# M617B.net
KiCad netlist of a schematic drawn in EAGLE
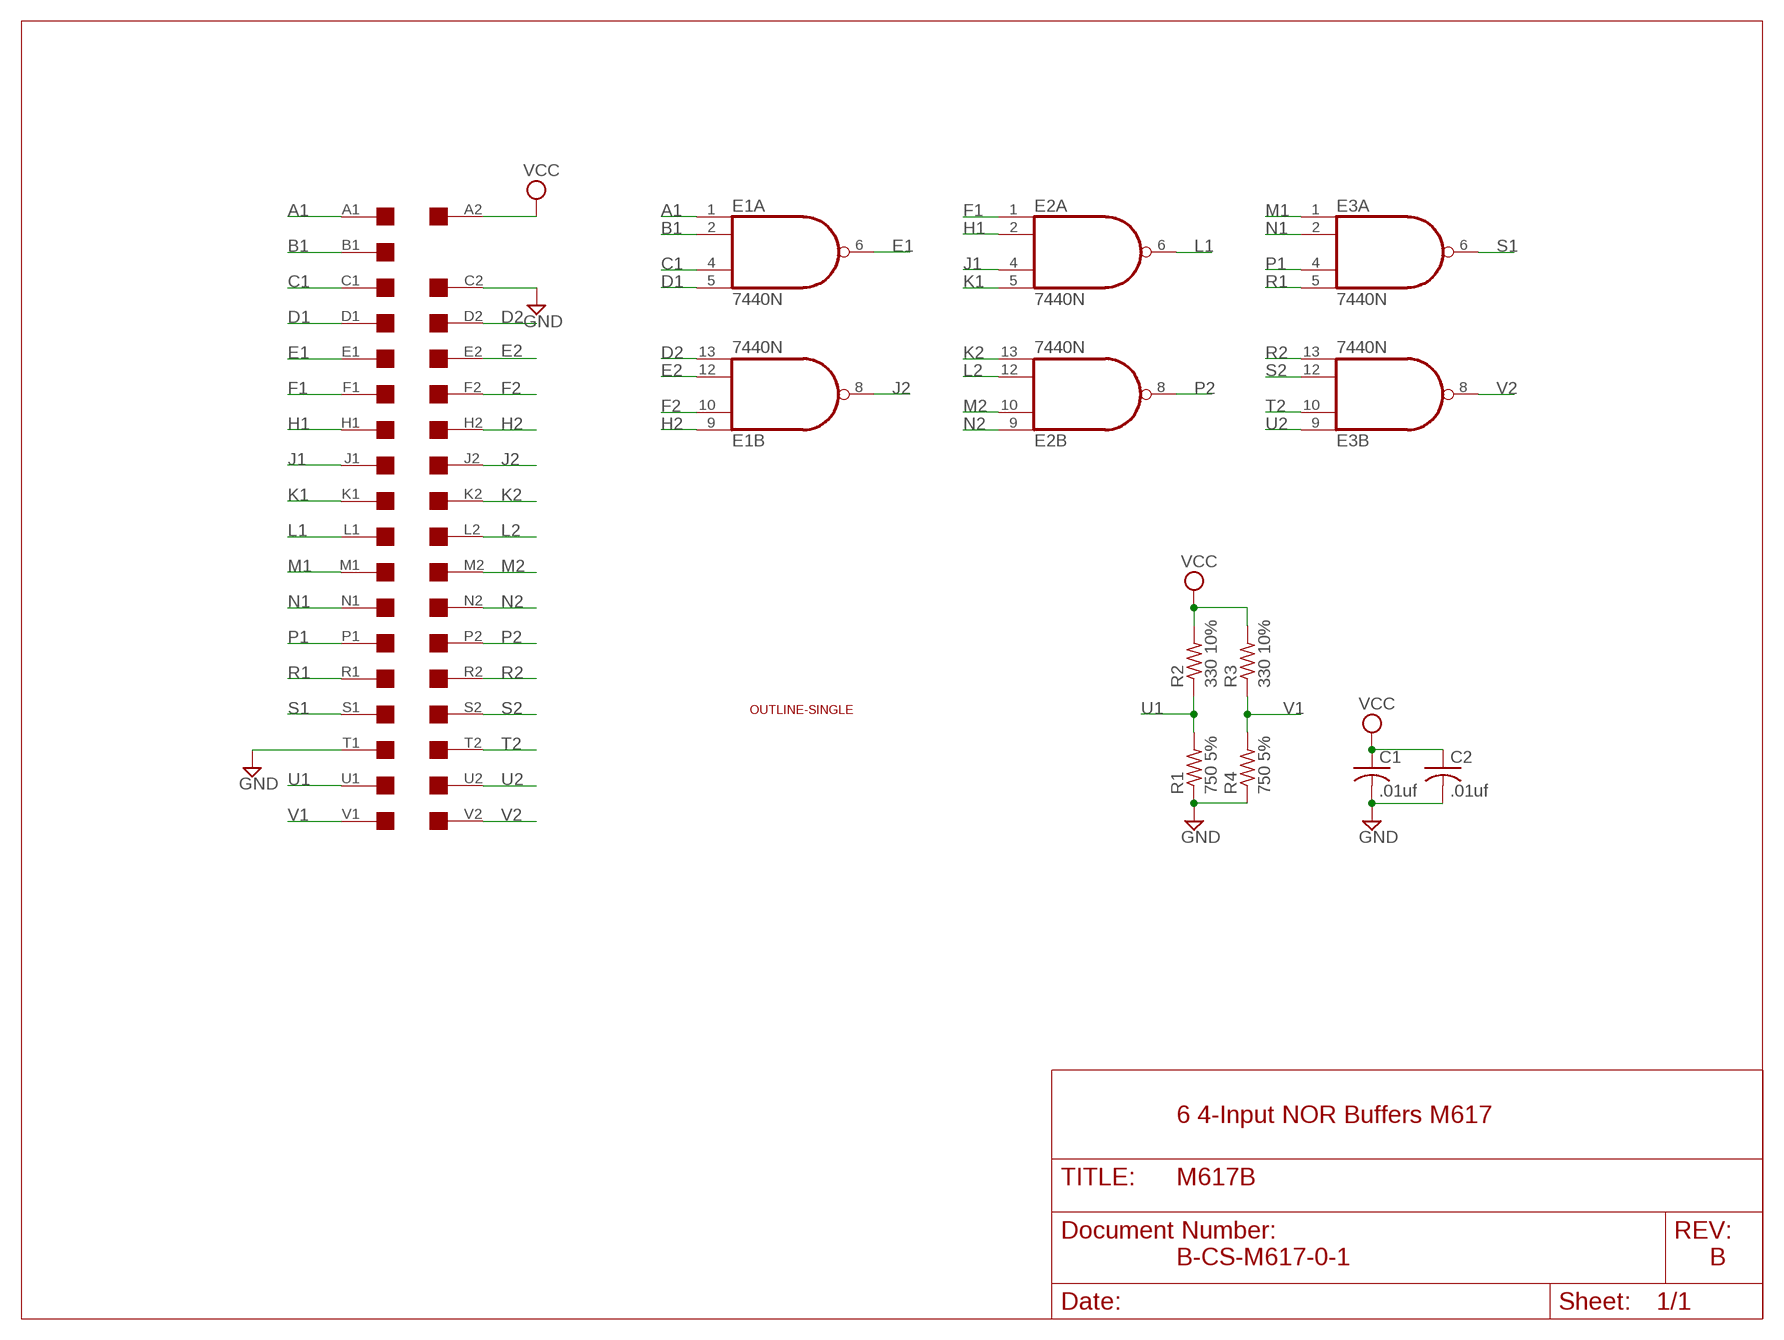
[diagram p0: schematic, sheet 1]

(export (version "E")
  (design (tool "Eeschema 10.0.6"))
  (components
    (comp (ref "C1")
      (value ".01uf")
      (footprint "eagle-import:C075-032X103")
      (libsource (lib "eagle-import") (part "C-US075-032X103"))
    )
    (comp (ref "C2")
      (value ".01uf")
      (footprint "eagle-import:C075-032X103")
      (libsource (lib "eagle-import") (part "C-US075-032X103"))
    )
    (comp (ref "E1")
      (value "7440N")
      (footprint "eagle-import:DIL14")
      (libsource (lib "eagle-import") (part "7420NS"))
    )
    (comp (ref "E2")
      (value "7440N")
      (footprint "eagle-import:DIL14")
      (libsource (lib "eagle-import") (part "7420NS"))
    )
    (comp (ref "E3")
      (value "7440N")
      (footprint "eagle-import:DIL14")
      (libsource (lib "eagle-import") (part "7420NS"))
    )
    (comp (ref "R1")
      (value "750 5%")
      (footprint "eagle-import:0207_15")
      (libsource (lib "eagle-import") (part "R-US_0207/15"))
    )
    (comp (ref "R2")
      (value "330 10%")
      (footprint "eagle-import:0207_15")
      (libsource (lib "eagle-import") (part "R-US_0207/15"))
    )
    (comp (ref "R3")
      (value "330 10%")
      (footprint "eagle-import:0207_15")
      (libsource (lib "eagle-import") (part "R-US_0207/15"))
    )
    (comp (ref "R4")
      (value "750 5%")
      (footprint "eagle-import:0207_15")
      (libsource (lib "eagle-import") (part "R-US_0207/15"))
    )
    (comp (ref "U$1")
      (value "SINGLE")
      (footprint "eagle-import:EDGE-CON2")
      (libsource (lib "eagle-import") (part "SINGLE"))
    )
    (comp (ref "U$4")
      (value "OUTLINE-SINGLE")
      (footprint "eagle-import:SINGLE")
      (libsource (lib "eagle-import") (part "OUTLINE-SINGLE"))
    )
  )
  (nets
    (net (code "1") (name "/A1") (class "Default")
      (node (ref "E1") (pin "1") (pinfunction "I0_1") (pintype "input"))
      (node (ref "U$1") (pin "A1") (pinfunction "1_A1") (pintype "bidirectional"))
    )
    (net (code "2") (name "/B1") (class "Default")
      (node (ref "E1") (pin "2") (pinfunction "I1_2") (pintype "input"))
      (node (ref "U$1") (pin "B1") (pinfunction "1_B1") (pintype "bidirectional"))
    )
    (net (code "3") (name "/C1") (class "Default")
      (node (ref "E1") (pin "4") (pinfunction "I2_4") (pintype "input"))
      (node (ref "U$1") (pin "C1") (pinfunction "1_C1") (pintype "bidirectional"))
    )
    (net (code "4") (name "/D1") (class "Default")
      (node (ref "E1") (pin "5") (pinfunction "I3_5") (pintype "input"))
      (node (ref "U$1") (pin "D1") (pinfunction "1_D1") (pintype "bidirectional"))
    )
    (net (code "5") (name "/D2") (class "Default")
      (node (ref "E1") (pin "13") (pinfunction "I3_13") (pintype "input"))
      (node (ref "U$1") (pin "D2") (pinfunction "1_D2") (pintype "bidirectional"))
    )
    (net (code "6") (name "/E1") (class "Default")
      (node (ref "E1") (pin "6") (pinfunction "O_6") (pintype "output"))
      (node (ref "U$1") (pin "E1") (pinfunction "1_E1") (pintype "bidirectional"))
    )
    (net (code "7") (name "/E2") (class "Default")
      (node (ref "E1") (pin "12") (pinfunction "I2_12") (pintype "input"))
      (node (ref "U$1") (pin "E2") (pinfunction "1_E2") (pintype "bidirectional"))
    )
    (net (code "8") (name "/F1") (class "Default")
      (node (ref "E2") (pin "1") (pinfunction "I0_1") (pintype "input"))
      (node (ref "U$1") (pin "F1") (pinfunction "1_F1") (pintype "bidirectional"))
    )
    (net (code "9") (name "/F2") (class "Default")
      (node (ref "E1") (pin "10") (pinfunction "I1_10") (pintype "input"))
      (node (ref "U$1") (pin "F2") (pinfunction "1_F2") (pintype "bidirectional"))
    )
    (net (code "10") (name "/H1") (class "Default")
      (node (ref "E2") (pin "2") (pinfunction "I1_2") (pintype "input"))
      (node (ref "U$1") (pin "H1") (pinfunction "1_H1") (pintype "bidirectional"))
    )
    (net (code "11") (name "/H2") (class "Default")
      (node (ref "E1") (pin "9") (pinfunction "I0_9") (pintype "input"))
      (node (ref "U$1") (pin "H2") (pinfunction "1_H2") (pintype "bidirectional"))
    )
    (net (code "12") (name "/J1") (class "Default")
      (node (ref "E2") (pin "4") (pinfunction "I2_4") (pintype "input"))
      (node (ref "U$1") (pin "J1") (pinfunction "1_J1") (pintype "bidirectional"))
    )
    (net (code "13") (name "/J2") (class "Default")
      (node (ref "E1") (pin "8") (pinfunction "O_8") (pintype "output"))
      (node (ref "U$1") (pin "J2") (pinfunction "1_J2") (pintype "bidirectional"))
    )
    (net (code "14") (name "/K1") (class "Default")
      (node (ref "E2") (pin "5") (pinfunction "I3_5") (pintype "input"))
      (node (ref "U$1") (pin "K1") (pinfunction "1_K1") (pintype "bidirectional"))
    )
    (net (code "15") (name "/K2") (class "Default")
      (node (ref "E2") (pin "13") (pinfunction "I3_13") (pintype "input"))
      (node (ref "U$1") (pin "K2") (pinfunction "1_K2") (pintype "bidirectional"))
    )
    (net (code "16") (name "/L1") (class "Default")
      (node (ref "E2") (pin "6") (pinfunction "O_6") (pintype "output"))
      (node (ref "U$1") (pin "L1") (pinfunction "1_L1") (pintype "bidirectional"))
    )
    (net (code "17") (name "/L2") (class "Default")
      (node (ref "E2") (pin "12") (pinfunction "I2_12") (pintype "input"))
      (node (ref "U$1") (pin "L2") (pinfunction "1_L2") (pintype "bidirectional"))
    )
    (net (code "18") (name "/M1") (class "Default")
      (node (ref "E3") (pin "1") (pinfunction "I0_1") (pintype "input"))
      (node (ref "U$1") (pin "M1") (pinfunction "1_M1") (pintype "bidirectional"))
    )
    (net (code "19") (name "/M2") (class "Default")
      (node (ref "E2") (pin "10") (pinfunction "I1_10") (pintype "input"))
      (node (ref "U$1") (pin "M2") (pinfunction "1_M2") (pintype "bidirectional"))
    )
    (net (code "20") (name "/N1") (class "Default")
      (node (ref "E3") (pin "2") (pinfunction "I1_2") (pintype "input"))
      (node (ref "U$1") (pin "N1") (pinfunction "1_N1") (pintype "bidirectional"))
    )
    (net (code "21") (name "/N2") (class "Default")
      (node (ref "E2") (pin "9") (pinfunction "I0_9") (pintype "input"))
      (node (ref "U$1") (pin "N2") (pinfunction "1_N2") (pintype "bidirectional"))
    )
    (net (code "22") (name "/P1") (class "Default")
      (node (ref "E3") (pin "4") (pinfunction "I2_4") (pintype "input"))
      (node (ref "U$1") (pin "P1") (pinfunction "1_P1") (pintype "bidirectional"))
    )
    (net (code "23") (name "/P2") (class "Default")
      (node (ref "E2") (pin "8") (pinfunction "O_8") (pintype "output"))
      (node (ref "U$1") (pin "P2") (pinfunction "1_P2") (pintype "bidirectional"))
    )
    (net (code "24") (name "/R1") (class "Default")
      (node (ref "E3") (pin "5") (pinfunction "I3_5") (pintype "input"))
      (node (ref "U$1") (pin "R1") (pinfunction "1_R1") (pintype "bidirectional"))
    )
    (net (code "25") (name "/R2") (class "Default")
      (node (ref "E3") (pin "13") (pinfunction "I3_13") (pintype "input"))
      (node (ref "U$1") (pin "R2") (pinfunction "1_R2") (pintype "bidirectional"))
    )
    (net (code "26") (name "/S1") (class "Default")
      (node (ref "E3") (pin "6") (pinfunction "O_6") (pintype "output"))
      (node (ref "U$1") (pin "S1") (pinfunction "1_S1") (pintype "bidirectional"))
    )
    (net (code "27") (name "/S2") (class "Default")
      (node (ref "E3") (pin "12") (pinfunction "I2_12") (pintype "input"))
      (node (ref "U$1") (pin "S2") (pinfunction "1_S2") (pintype "bidirectional"))
    )
    (net (code "28") (name "/T2") (class "Default")
      (node (ref "E3") (pin "10") (pinfunction "I1_10") (pintype "input"))
      (node (ref "U$1") (pin "T2") (pinfunction "1_T2") (pintype "bidirectional"))
    )
    (net (code "29") (name "/U1") (class "Default")
      (node (ref "R1") (pin "2") (pinfunction "2_2") (pintype "passive"))
      (node (ref "R2") (pin "1") (pinfunction "1_1") (pintype "passive"))
      (node (ref "U$1") (pin "U1") (pinfunction "1_U1") (pintype "bidirectional"))
    )
    (net (code "30") (name "/U2") (class "Default")
      (node (ref "E3") (pin "9") (pinfunction "I0_9") (pintype "input"))
      (node (ref "U$1") (pin "U2") (pinfunction "1_U2") (pintype "bidirectional"))
    )
    (net (code "31") (name "/V1") (class "Default")
      (node (ref "R3") (pin "1") (pinfunction "1_1") (pintype "passive"))
      (node (ref "R4") (pin "2") (pinfunction "2_2") (pintype "passive"))
      (node (ref "U$1") (pin "V1") (pinfunction "1_V1") (pintype "bidirectional"))
    )
    (net (code "32") (name "/V2") (class "Default")
      (node (ref "E3") (pin "8") (pinfunction "O_8") (pintype "output"))
      (node (ref "U$1") (pin "V2") (pinfunction "1_V2") (pintype "bidirectional"))
    )
    (net (code "33") (name "GND") (class "Default")
      (node (ref "C1") (pin "2") (pinfunction "2_2") (pintype "passive"))
      (node (ref "C2") (pin "2") (pinfunction "2_2") (pintype "passive"))
      (node (ref "R1") (pin "1") (pinfunction "1_1") (pintype "passive"))
      (node (ref "R4") (pin "1") (pinfunction "1_1") (pintype "passive"))
      (node (ref "U$1") (pin "C2") (pinfunction "1_C2") (pintype "bidirectional"))
      (node (ref "U$1") (pin "T1") (pinfunction "1_T1") (pintype "bidirectional"))
    )
    (net (code "34") (name "VCC") (class "Default")
      (node (ref "C1") (pin "1") (pinfunction "1_1") (pintype "passive"))
      (node (ref "C2") (pin "1") (pinfunction "1_1") (pintype "passive"))
      (node (ref "R2") (pin "2") (pinfunction "2_2") (pintype "passive"))
      (node (ref "R3") (pin "2") (pinfunction "2_2") (pintype "passive"))
      (node (ref "U$1") (pin "A2") (pinfunction "1_A2") (pintype "bidirectional"))
    )
  )
)
